# MCU.net
KiCad netlist of a schematic drawn in Altium Designer
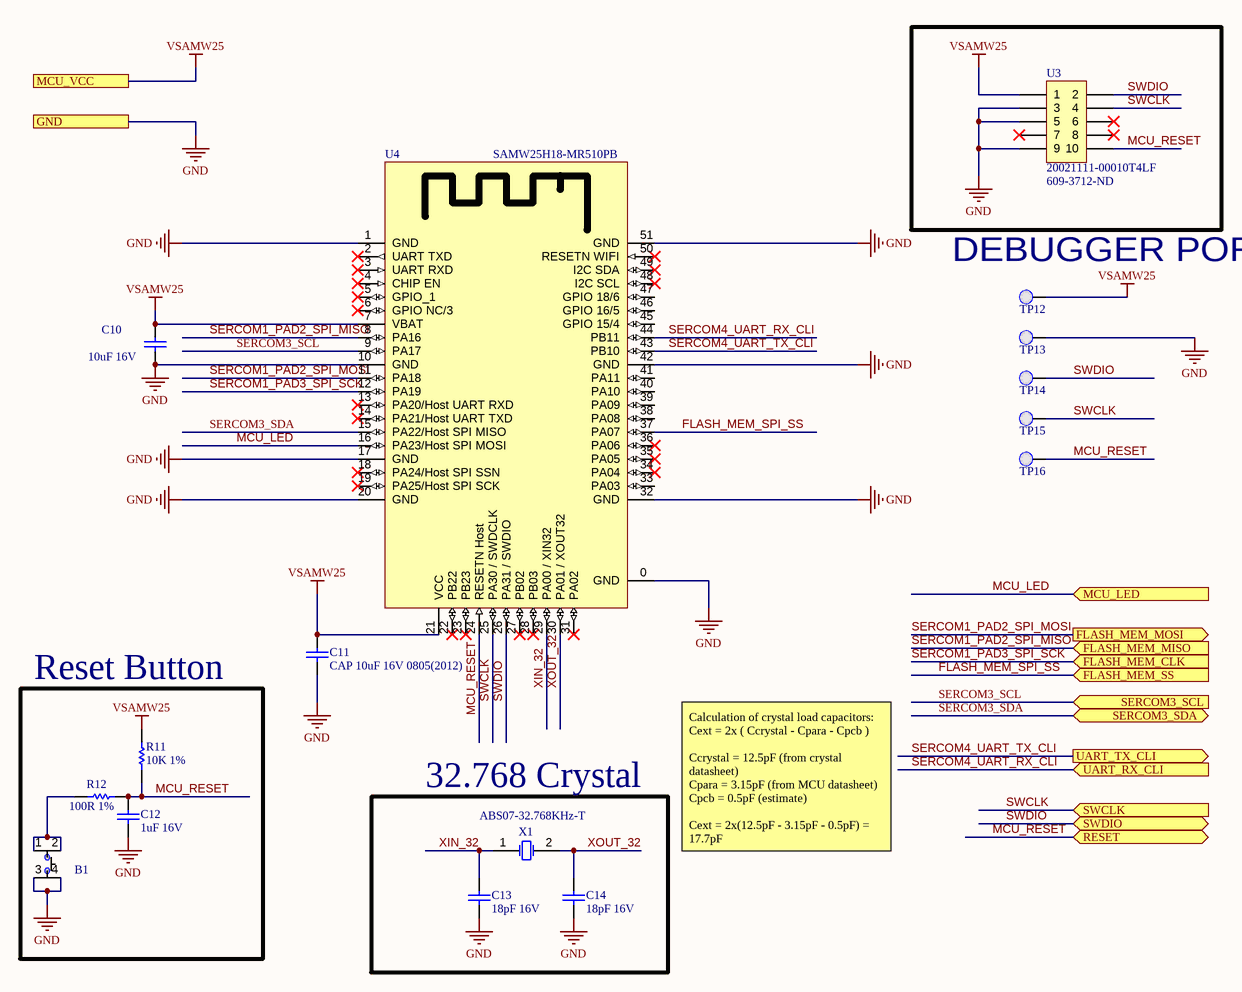
[diagram p0: MCU.SchDoc]

(export (version "E")
  (design (tool "Eeschema 10.0.6"))
  (components
    (comp (ref "B1")
      (value "PTS810 SJK 250 SMTR LFS")
      (footprint "PTS810 SJK 250 SMTR LFS")
      (description "SWITCH TACTILE SPST-NO 0.05A 16V Tactile Switch SPST-NO Top Actuated Surface Mount")
      (fields
        (field (name "MANUFACTURER") "ITT /  C&K Components")
        (field (name "MANUFACTURER PART NUMBER") "PTS810SJK250SMTRLFS")
      )
      (libsource (lib "Schematics") (part "PTS810 SJK 250 SMTR LFS"))
    )
    (comp (ref "C10")
      (value "10uF 16V")
      (footprint "CAPC0805(2012)145_N")
      (description "CAP 10uF 16V ±10% 0805 (2012 Metric) Thickness 1.45mm SMD")
      (fields (field (name "TOLERANCE") "Â±10%"))
      (libsource (lib "Altium Content Vault") (part "CAP"))
    )
    (comp (ref "C11")
      (value "CAP 10uF 16V 0805(2012)")
      (footprint "CAPC0805(2012)145_N")
      (description "CAP 10uF 16V ±10% 0805 (2012 Metric) Thickness 1.45mm SMD")
      (fields (field (name "TOLERANCE") "Â±10%"))
      (libsource (lib "Altium Content Vault") (part "CAP"))
    )
    (comp (ref "C12")
      (value "1uF 16V")
      (footprint "CAPC0603(1608)100_N")
      (description "CAP 1uF 16V ±5% 0603 (1608 Metric) Thickness 1mm SMD")
      (fields (field (name "TOLERANCE") "Â±5%"))
      (libsource (lib "Altium Content Vault") (part "CAP"))
    )
    (comp (ref "C13")
      (value "18pF 16V")
      (footprint "CAPC0603(1608)100_N")
      (description "CAP 18pF 16V ±5% 0603 (1608 Metric) Thickness 1mm SMD")
      (fields (field (name "TOLERANCE") "Â±5%"))
      (libsource (lib "Altium Content Vault") (part "CAP"))
    )
    (comp (ref "C14")
      (value "18pF 16V")
      (footprint "CAPC0603(1608)100_N")
      (description "CAP 18pF 16V ±5% 0603 (1608 Metric) Thickness 1mm SMD")
      (fields (field (name "TOLERANCE") "Â±5%"))
      (libsource (lib "Altium Content Vault") (part "CAP"))
    )
    (comp (ref "R11")
      (value "10K 1%")
      (footprint "RESC0603(1608)_N")
      (description "10K 0.1W 1% 0603 (1608 Metric)  SMD")
      (fields (field (name "POWER") "0.1 W") (field (name "TOLERANCE") "1 %"))
      (libsource (lib "Altium Content Vault") (part "RES"))
    )
    (comp (ref "R12")
      (value "100R 1%")
      (footprint "RESC0603(1608)_N")
      (description "100R 0.1W 1% 0603 (1608 Metric)  SMD")
      (fields (field (name "TOLERANCE") "1 %") (field (name "POWER") "0.1 W"))
      (libsource (lib "Altium Content Vault") (part "RES"))
    )
    (comp (ref "TP12")
      (value "0.1\" Pad")
      (footprint "PCBComponent")
      (libsource (lib "Components - 12.02.20 - 18.05") (part "0.1{dblquote} Pad-A.4"))
    )
    (comp (ref "TP13")
      (value "0.1\" Pad")
      (footprint "PCBComponent")
      (libsource (lib "Components - 12.02.20 - 18.05") (part "0.1{dblquote} Pad-A.4"))
    )
    (comp (ref "TP14")
      (value "0.1\" Pad")
      (footprint "PCBComponent")
      (libsource (lib "Components - 12.02.20 - 18.05") (part "0.1{dblquote} Pad-A.4"))
    )
    (comp (ref "TP15")
      (value "0.1\" Pad")
      (footprint "PCBComponent")
      (libsource (lib "Components - 12.02.20 - 18.05") (part "0.1{dblquote} Pad-A.4"))
    )
    (comp (ref "TP16")
      (value "0.1\" Pad")
      (footprint "PCBComponent")
      (libsource (lib "Components - 12.02.20 - 18.05") (part "0.1{dblquote} Pad-A.4"))
    )
    (comp (ref "U3")
      (value "20021111-00010T4LF")
      (footprint "20021111-00010T4LF")
      (description "CONN HEADER 10POS UNSHD VERT T/H")
      (fields
        (field (name "MANUFACTURER") "Amphenol / FCI")
        (field (name "SUPPLIER PART NUMBER 1") "609-3712-ND")
      )
      (libsource (lib "Schematics") (part "20021111-00010T4LF"))
    )
    (comp (ref "U4")
      (value "SAMW25H18-MR510PB")
      (footprint "SAMW25H18-MR510PB")
      (description "RF TXRX MODULE WIFI TRACE ANT")
      (fields
        (field (name "MANUFACTURER") "Atmel")
        (field (name "MANUFACTURER PART NUMBER") "ATSAMW25H18-MR510PB")
      )
      (libsource (lib "Schematics") (part "SAMW25H18-MR510PB"))
    )
    (comp (ref "X1")
      (value "ABS07-32.768KHz-T")
      (footprint "ABRA-ABS07-2_V")
      (description "Crystal, 32.768 kHz, 12.5 pF, -40 to 85 degC, SMD Low Profile 3.2 x 1.5 x 0.9 mm, Tape and Reel")
      (fields (field (name "MANUFACTURER") "Abracon"))
      (libsource (lib "Altium Content Vault") (part "ABRA-ABS07-2"))
    )
  )
  (nets
    (net (code "1") (name "/FLASH_MEM_SPI_SS") (class "Default")
      (node (ref "U4") (pin "37") (pinfunction "PA07_37") (pintype "bidirectional"))
    )
    (net (code "2") (name "/MCU_LED") (class "Default")
      (node (ref "U4") (pin "16") (pinfunction "PA23/Host_SPI_MOSI_16") (pintype "bidirectional"))
    )
    (net (code "3") (name "/MCU_RESET") (class "Default")
      (node (ref "C12") (pin "2") (pinfunction "2_2") (pintype "passive"))
      (node (ref "R11") (pin "1") (pinfunction "1_1") (pintype "passive"))
      (node (ref "R12") (pin "2") (pinfunction "2_2") (pintype "passive"))
      (node (ref "TP16") (pin "1") (pinfunction "PAD_1") (pintype "passive"))
      (node (ref "U3") (pin "10") (pinfunction "10_10") (pintype "passive"))
      (node (ref "U4") (pin "24") (pinfunction "RESETN_Host_24") (pintype "input"))
    )
    (net (code "4") (name "/SERCOM1_PAD2_SPI_MISO") (class "Default")
      (node (ref "U4") (pin "8") (pinfunction "PA16_8") (pintype "bidirectional"))
    )
    (net (code "5") (name "/SERCOM1_PAD2_SPI_MOSI") (class "Default")
      (node (ref "U4") (pin "11") (pinfunction "PA18_11") (pintype "bidirectional"))
    )
    (net (code "6") (name "/SERCOM1_PAD3_SPI_SCK") (class "Default")
      (node (ref "U4") (pin "12") (pinfunction "PA19_12") (pintype "bidirectional"))
    )
    (net (code "7") (name "/SERCOM3_SCL") (class "Default")
      (node (ref "U4") (pin "9") (pinfunction "PA17_9") (pintype "bidirectional"))
    )
    (net (code "8") (name "/SERCOM3_SDA") (class "Default")
      (node (ref "U4") (pin "15") (pinfunction "PA22/Host_SPI_MISO_15") (pintype "bidirectional"))
    )
    (net (code "9") (name "/SERCOM4_UART_RX_CLI") (class "Default")
      (node (ref "U4") (pin "44") (pinfunction "PB11_44") (pintype "bidirectional"))
    )
    (net (code "10") (name "/SERCOM4_UART_TX_CLI") (class "Default")
      (node (ref "U4") (pin "43") (pinfunction "PB10_43") (pintype "bidirectional"))
    )
    (net (code "11") (name "/SWCLK") (class "Default")
      (node (ref "TP15") (pin "1") (pinfunction "PAD_1") (pintype "passive"))
      (node (ref "U3") (pin "4") (pinfunction "4_4") (pintype "passive"))
      (node (ref "U4") (pin "25") (pinfunction "PA30_/_SWDCLK_25") (pintype "bidirectional"))
    )
    (net (code "12") (name "/SWDIO") (class "Default")
      (node (ref "TP14") (pin "1") (pinfunction "PAD_1") (pintype "passive"))
      (node (ref "U3") (pin "2") (pinfunction "2_2") (pintype "passive"))
      (node (ref "U4") (pin "26") (pinfunction "PA31_/_SWDIO_26") (pintype "bidirectional"))
    )
    (net (code "13") (name "/XIN_32") (class "Default")
      (node (ref "C13") (pin "2") (pinfunction "2_2") (pintype "passive"))
      (node (ref "U4") (pin "29") (pinfunction "PA00_/_XIN32_29") (pintype "bidirectional"))
      (node (ref "X1") (pin "1") (pinfunction "X1_1") (pintype "passive"))
    )
    (net (code "14") (name "/XOUT_32") (class "Default")
      (node (ref "C14") (pin "2") (pinfunction "2_2") (pintype "passive"))
      (node (ref "U4") (pin "30") (pinfunction "PA01_/_XOUT32_30") (pintype "bidirectional"))
      (node (ref "X1") (pin "2") (pinfunction "X2_2") (pintype "passive"))
    )
    (net (code "15") (name "GND") (class "Default")
      (node (ref "B1") (pin "3") (pinfunction "3_3") (pintype "power_in"))
      (node (ref "B1") (pin "4") (pinfunction "4_4") (pintype "power_in"))
      (node (ref "C10") (pin "1") (pinfunction "1_1") (pintype "passive"))
      (node (ref "C11") (pin "1") (pinfunction "1_1") (pintype "passive"))
      (node (ref "C12") (pin "1") (pinfunction "1_1") (pintype "passive"))
      (node (ref "C13") (pin "1") (pinfunction "1_1") (pintype "passive"))
      (node (ref "C14") (pin "1") (pinfunction "1_1") (pintype "passive"))
      (node (ref "TP13") (pin "1") (pinfunction "PAD_1") (pintype "passive"))
      (node (ref "U3") (pin "3") (pinfunction "3_3") (pintype "passive"))
      (node (ref "U3") (pin "5") (pinfunction "5_5") (pintype "passive"))
      (node (ref "U3") (pin "9") (pinfunction "9_9") (pintype "passive"))
      (node (ref "U4") (pin "0") (pinfunction "GND_0") (pintype "power_in"))
      (node (ref "U4") (pin "1") (pinfunction "GND_1") (pintype "power_in"))
      (node (ref "U4") (pin "10") (pinfunction "GND_10") (pintype "power_in"))
      (node (ref "U4") (pin "17") (pinfunction "GND_17") (pintype "power_in"))
      (node (ref "U4") (pin "20") (pinfunction "GND_20") (pintype "power_in"))
      (node (ref "U4") (pin "32") (pinfunction "GND_32") (pintype "power_in"))
      (node (ref "U4") (pin "42") (pinfunction "GND_42") (pintype "power_in"))
      (node (ref "U4") (pin "51") (pinfunction "GND_51") (pintype "power_in"))
    )
    (net (code "16") (name "Net-(B1-Pad1)") (class "Default")
      (node (ref "B1") (pin "1") (pinfunction "1_1") (pintype "power_in"))
      (node (ref "B1") (pin "2") (pinfunction "2_2") (pintype "power_in"))
      (node (ref "R12") (pin "1") (pinfunction "1_1") (pintype "passive"))
    )
    (net (code "17") (name "VSAMW25") (class "Default")
      (node (ref "C10") (pin "2") (pinfunction "2_2") (pintype "passive"))
      (node (ref "C11") (pin "2") (pinfunction "2_2") (pintype "passive"))
      (node (ref "R11") (pin "2") (pinfunction "2_2") (pintype "passive"))
      (node (ref "TP12") (pin "1") (pinfunction "PAD_1") (pintype "passive"))
      (node (ref "U3") (pin "1") (pinfunction "1_1") (pintype "passive"))
      (node (ref "U4") (pin "21") (pinfunction "VCC_21") (pintype "power_in"))
      (node (ref "U4") (pin "7") (pinfunction "VBAT_7") (pintype "power_in"))
    )
    (net (code "18") (name "unconnected-(U3-Pad6)") (class "Default")
      (node (ref "U3") (pin "6") (pinfunction "6_6") (pintype "passive+no_connect"))
    )
    (net (code "19") (name "unconnected-(U3-Pad7)") (class "Default")
      (node (ref "U3") (pin "7") (pinfunction "7_7") (pintype "passive+no_connect"))
    )
    (net (code "20") (name "unconnected-(U3-Pad8)") (class "Default")
      (node (ref "U3") (pin "8") (pinfunction "8_8") (pintype "passive+no_connect"))
    )
    (net (code "21") (name "unconnected-(U4-CHIP_EN-Pad4)") (class "Default")
      (node (ref "U4") (pin "4") (pinfunction "CHIP_EN_4") (pintype "input+no_connect"))
    )
    (net (code "22") (name "unconnected-(U4-GPIO_1-Pad5)") (class "Default")
      (node (ref "U4") (pin "5") (pinfunction "GPIO_1_5") (pintype "bidirectional+no_connect"))
    )
    (net (code "23") (name "unconnected-(U4-GPIO_15{slash}4-Pad45)") (class "Default")
      (node (ref "U4") (pin "45") (pinfunction "GPIO_15/4_45") (pintype "bidirectional"))
    )
    (net (code "24") (name "unconnected-(U4-GPIO_16{slash}5-Pad46)") (class "Default")
      (node (ref "U4") (pin "46") (pinfunction "GPIO_16/5_46") (pintype "bidirectional"))
    )
    (net (code "25") (name "unconnected-(U4-GPIO_18{slash}6-Pad47)") (class "Default")
      (node (ref "U4") (pin "47") (pinfunction "GPIO_18/6_47") (pintype "bidirectional"))
    )
    (net (code "26") (name "unconnected-(U4-GPIO_NC{slash}3-Pad6)") (class "Default")
      (node (ref "U4") (pin "6") (pinfunction "GPIO_NC/3_6") (pintype "bidirectional+no_connect"))
    )
    (net (code "27") (name "unconnected-(U4-I2C_SCL-Pad48)") (class "Default")
      (node (ref "U4") (pin "48") (pinfunction "I2C_SCL_48") (pintype "bidirectional+no_connect"))
    )
    (net (code "28") (name "unconnected-(U4-I2C_SDA-Pad49)") (class "Default")
      (node (ref "U4") (pin "49") (pinfunction "I2C_SDA_49") (pintype "bidirectional+no_connect"))
    )
    (net (code "29") (name "unconnected-(U4-PA02-Pad31)") (class "Default")
      (node (ref "U4") (pin "31") (pinfunction "PA02_31") (pintype "bidirectional+no_connect"))
    )
    (net (code "30") (name "unconnected-(U4-PA03-Pad33)") (class "Default")
      (node (ref "U4") (pin "33") (pinfunction "PA03_33") (pintype "bidirectional"))
    )
    (net (code "31") (name "unconnected-(U4-PA04-Pad34)") (class "Default")
      (node (ref "U4") (pin "34") (pinfunction "PA04_34") (pintype "bidirectional+no_connect"))
    )
    (net (code "32") (name "unconnected-(U4-PA05-Pad35)") (class "Default")
      (node (ref "U4") (pin "35") (pinfunction "PA05_35") (pintype "bidirectional+no_connect"))
    )
    (net (code "33") (name "unconnected-(U4-PA06-Pad36)") (class "Default")
      (node (ref "U4") (pin "36") (pinfunction "PA06_36") (pintype "bidirectional+no_connect"))
    )
    (net (code "34") (name "unconnected-(U4-PA08-Pad38)") (class "Default")
      (node (ref "U4") (pin "38") (pinfunction "PA08_38") (pintype "bidirectional"))
    )
    (net (code "35") (name "unconnected-(U4-PA09-Pad39)") (class "Default")
      (node (ref "U4") (pin "39") (pinfunction "PA09_39") (pintype "bidirectional"))
    )
    (net (code "36") (name "unconnected-(U4-PA10-Pad40)") (class "Default")
      (node (ref "U4") (pin "40") (pinfunction "PA10_40") (pintype "bidirectional"))
    )
    (net (code "37") (name "unconnected-(U4-PA11-Pad41)") (class "Default")
      (node (ref "U4") (pin "41") (pinfunction "PA11_41") (pintype "bidirectional"))
    )
    (net (code "38") (name "unconnected-(U4-PA20{slash}Host_UART_RXD-Pad13)") (class "Default")
      (node (ref "U4") (pin "13") (pinfunction "PA20/Host_UART_RXD_13") (pintype "bidirectional+no_connect"))
    )
    (net (code "39") (name "unconnected-(U4-PA21{slash}Host_UART_TXD-Pad14)") (class "Default")
      (node (ref "U4") (pin "14") (pinfunction "PA21/Host_UART_TXD_14") (pintype "bidirectional+no_connect"))
    )
    (net (code "40") (name "unconnected-(U4-PA24{slash}Host_SPI_SSN-Pad18)") (class "Default")
      (node (ref "U4") (pin "18") (pinfunction "PA24/Host_SPI_SSN_18") (pintype "bidirectional+no_connect"))
    )
    (net (code "41") (name "unconnected-(U4-PA25{slash}Host_SPI_SCK-Pad19)") (class "Default")
      (node (ref "U4") (pin "19") (pinfunction "PA25/Host_SPI_SCK_19") (pintype "bidirectional+no_connect"))
    )
    (net (code "42") (name "unconnected-(U4-PB02-Pad27)") (class "Default")
      (node (ref "U4") (pin "27") (pinfunction "PB02_27") (pintype "bidirectional+no_connect"))
    )
    (net (code "43") (name "unconnected-(U4-PB03-Pad28)") (class "Default")
      (node (ref "U4") (pin "28") (pinfunction "PB03_28") (pintype "bidirectional+no_connect"))
    )
    (net (code "44") (name "unconnected-(U4-PB22-Pad22)") (class "Default")
      (node (ref "U4") (pin "22") (pinfunction "PB22_22") (pintype "bidirectional+no_connect"))
    )
    (net (code "45") (name "unconnected-(U4-PB23-Pad23)") (class "Default")
      (node (ref "U4") (pin "23") (pinfunction "PB23_23") (pintype "bidirectional+no_connect"))
    )
    (net (code "46") (name "unconnected-(U4-RESETN_WIFI-Pad50)") (class "Default")
      (node (ref "U4") (pin "50") (pinfunction "RESETN_WIFI_50") (pintype "input+no_connect"))
    )
    (net (code "47") (name "unconnected-(U4-UART_RXD-Pad3)") (class "Default")
      (node (ref "U4") (pin "3") (pinfunction "UART_RXD_3") (pintype "input+no_connect"))
    )
    (net (code "48") (name "unconnected-(U4-UART_TXD-Pad2)") (class "Default")
      (node (ref "U4") (pin "2") (pinfunction "UART_TXD_2") (pintype "output+no_connect"))
    )
  )
)
